# 20x20_adapter.net
KiCad netlist of a schematic drawn in EAGLE
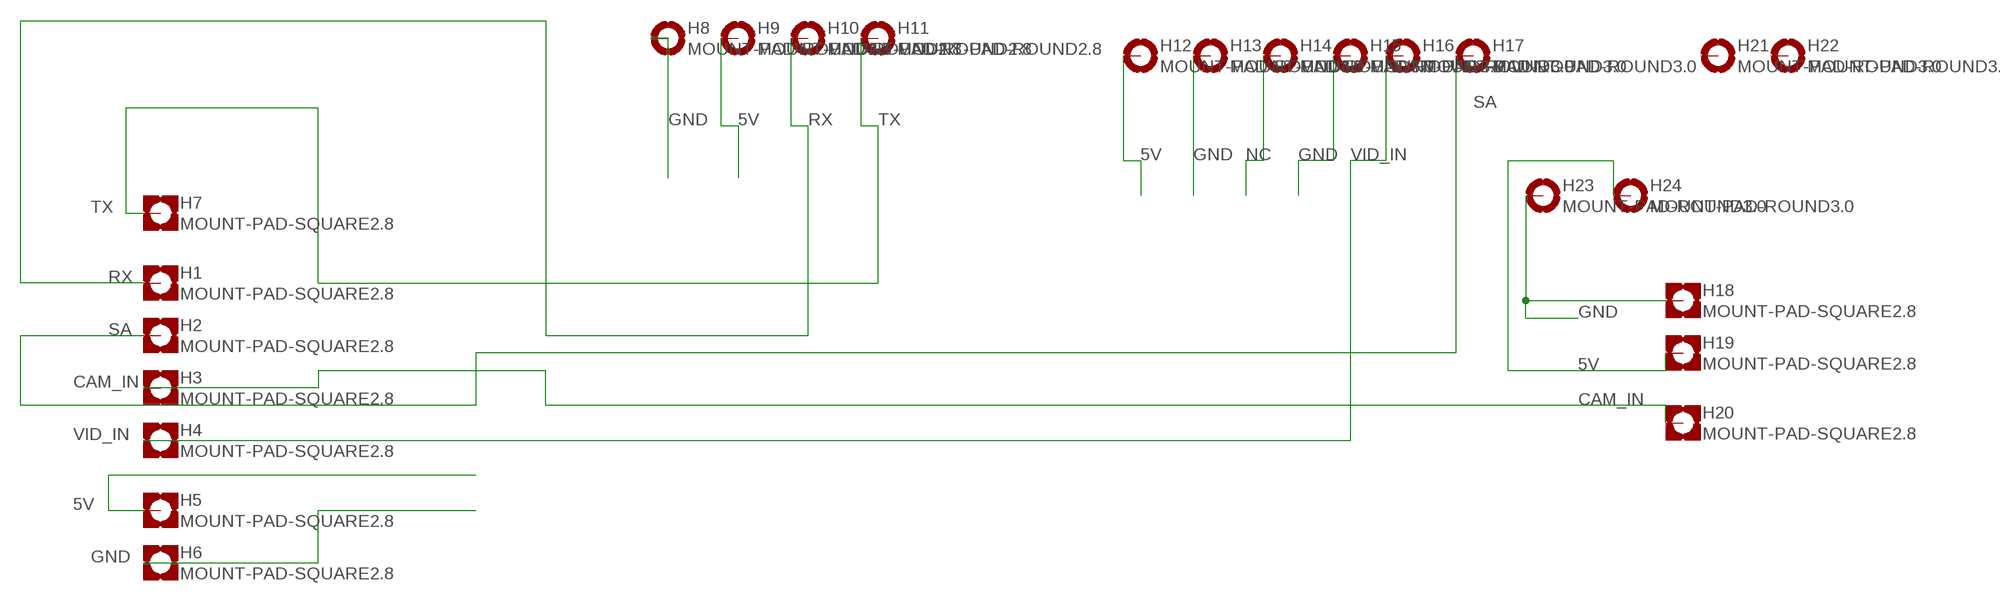
[diagram p0: schematic, sheet 1]

(export (version "E")
  (design (tool "Eeschema 10.0.6"))
  (components
    (comp (ref "H1")
      (value "MOUNT-PAD-SQUARE2.8")
      (footprint "eagle-import:2,8-PAD-SQUARE")
      (libsource (lib "eagle-import") (part "MOUNT-PAD-SQUARE2.8"))
    )
    (comp (ref "H2")
      (value "MOUNT-PAD-SQUARE2.8")
      (footprint "eagle-import:2,8-PAD-SQUARE")
      (libsource (lib "eagle-import") (part "MOUNT-PAD-SQUARE2.8"))
    )
    (comp (ref "H3")
      (value "MOUNT-PAD-SQUARE2.8")
      (footprint "eagle-import:2,8-PAD-SQUARE")
      (libsource (lib "eagle-import") (part "MOUNT-PAD-SQUARE2.8"))
    )
    (comp (ref "H4")
      (value "MOUNT-PAD-SQUARE2.8")
      (footprint "eagle-import:2,8-PAD-SQUARE")
      (libsource (lib "eagle-import") (part "MOUNT-PAD-SQUARE2.8"))
    )
    (comp (ref "H5")
      (value "MOUNT-PAD-SQUARE2.8")
      (footprint "eagle-import:2,8-PAD-SQUARE")
      (libsource (lib "eagle-import") (part "MOUNT-PAD-SQUARE2.8"))
    )
    (comp (ref "H6")
      (value "MOUNT-PAD-SQUARE2.8")
      (footprint "eagle-import:2,8-PAD-SQUARE")
      (libsource (lib "eagle-import") (part "MOUNT-PAD-SQUARE2.8"))
    )
    (comp (ref "H7")
      (value "MOUNT-PAD-SQUARE2.8")
      (footprint "eagle-import:2,8-PAD-SQUARE")
      (libsource (lib "eagle-import") (part "MOUNT-PAD-SQUARE2.8"))
    )
    (comp (ref "H8")
      (value "MOUNT-PAD-ROUND2.8")
      (footprint "eagle-import:1,0-PAD")
      (libsource (lib "eagle-import") (part "MOUNT-PAD-ROUND2.8"))
    )
    (comp (ref "H9")
      (value "MOUNT-PAD-ROUND2.8")
      (footprint "eagle-import:1,0-PAD")
      (libsource (lib "eagle-import") (part "MOUNT-PAD-ROUND2.8"))
    )
    (comp (ref "H10")
      (value "MOUNT-PAD-ROUND2.8")
      (footprint "eagle-import:1,0-PAD")
      (libsource (lib "eagle-import") (part "MOUNT-PAD-ROUND2.8"))
    )
    (comp (ref "H11")
      (value "MOUNT-PAD-ROUND2.8")
      (footprint "eagle-import:1,0-PAD")
      (libsource (lib "eagle-import") (part "MOUNT-PAD-ROUND2.8"))
    )
    (comp (ref "H12")
      (value "MOUNT-PAD-ROUND3.0")
      (footprint "eagle-import:3,0-PAD")
      (libsource (lib "eagle-import") (part "MOUNT-PAD-ROUND3.0"))
    )
    (comp (ref "H13")
      (value "MOUNT-PAD-ROUND3.0")
      (footprint "eagle-import:3,0-PAD")
      (libsource (lib "eagle-import") (part "MOUNT-PAD-ROUND3.0"))
    )
    (comp (ref "H14")
      (value "MOUNT-PAD-ROUND3.0")
      (footprint "eagle-import:3,0-PAD")
      (libsource (lib "eagle-import") (part "MOUNT-PAD-ROUND3.0"))
    )
    (comp (ref "H15")
      (value "MOUNT-PAD-ROUND3.0")
      (footprint "eagle-import:3,0-PAD")
      (libsource (lib "eagle-import") (part "MOUNT-PAD-ROUND3.0"))
    )
    (comp (ref "H16")
      (value "MOUNT-PAD-ROUND3.0")
      (footprint "eagle-import:3,0-PAD")
      (libsource (lib "eagle-import") (part "MOUNT-PAD-ROUND3.0"))
    )
    (comp (ref "H17")
      (value "MOUNT-PAD-ROUND3.0")
      (footprint "eagle-import:3,0-PAD")
      (libsource (lib "eagle-import") (part "MOUNT-PAD-ROUND3.0"))
    )
    (comp (ref "H18")
      (value "MOUNT-PAD-SQUARE2.8")
      (footprint "eagle-import:2,8-PAD-SQUARE")
      (libsource (lib "eagle-import") (part "MOUNT-PAD-SQUARE2.8"))
    )
    (comp (ref "H19")
      (value "MOUNT-PAD-SQUARE2.8")
      (footprint "eagle-import:2,8-PAD-SQUARE")
      (libsource (lib "eagle-import") (part "MOUNT-PAD-SQUARE2.8"))
    )
    (comp (ref "H20")
      (value "MOUNT-PAD-SQUARE2.8")
      (footprint "eagle-import:2,8-PAD-SQUARE")
      (libsource (lib "eagle-import") (part "MOUNT-PAD-SQUARE2.8"))
    )
    (comp (ref "H21")
      (value "MOUNT-PAD-ROUND3.0")
      (footprint "eagle-import:3,0-PAD")
      (libsource (lib "eagle-import") (part "MOUNT-PAD-ROUND3.0"))
    )
    (comp (ref "H22")
      (value "MOUNT-PAD-ROUND3.0")
      (footprint "eagle-import:3,0-PAD")
      (libsource (lib "eagle-import") (part "MOUNT-PAD-ROUND3.0"))
    )
    (comp (ref "H23")
      (value "MOUNT-PAD-ROUND3.0")
      (footprint "eagle-import:3,0-PAD")
      (libsource (lib "eagle-import") (part "MOUNT-PAD-ROUND3.0"))
    )
    (comp (ref "H24")
      (value "MOUNT-PAD-ROUND3.0")
      (footprint "eagle-import:3,0-PAD")
      (libsource (lib "eagle-import") (part "MOUNT-PAD-ROUND3.0"))
    )
  )
  (nets
    (net (code "1") (name "/5V") (class "Default")
      (node (ref "H12") (pin "B0,5") (pinfunction "MOUNT_B0,5") (pintype "passive"))
      (node (ref "H19") (pin "P$2") (pinfunction "MOUNT_P$2") (pintype "passive"))
      (node (ref "H24") (pin "B0,5") (pinfunction "MOUNT_B0,5") (pintype "passive"))
      (node (ref "H5") (pin "P$2") (pinfunction "MOUNT_P$2") (pintype "passive"))
      (node (ref "H9") (pin "B1,0") (pinfunction "MOUNT_B1,0") (pintype "passive"))
    )
    (net (code "2") (name "/CAM_IN") (class "Default")
      (node (ref "H20") (pin "P$2") (pinfunction "MOUNT_P$2") (pintype "passive"))
      (node (ref "H3") (pin "P$2") (pinfunction "MOUNT_P$2") (pintype "passive"))
    )
    (net (code "3") (name "/GND") (class "Default")
      (node (ref "H13") (pin "B0,5") (pinfunction "MOUNT_B0,5") (pintype "passive"))
      (node (ref "H15") (pin "B0,5") (pinfunction "MOUNT_B0,5") (pintype "passive"))
      (node (ref "H18") (pin "P$2") (pinfunction "MOUNT_P$2") (pintype "passive"))
      (node (ref "H23") (pin "B0,5") (pinfunction "MOUNT_B0,5") (pintype "passive"))
      (node (ref "H6") (pin "P$2") (pinfunction "MOUNT_P$2") (pintype "passive"))
      (node (ref "H8") (pin "B1,0") (pinfunction "MOUNT_B1,0") (pintype "passive"))
    )
    (net (code "4") (name "/NC") (class "Default")
      (node (ref "H14") (pin "B0,5") (pinfunction "MOUNT_B0,5") (pintype "passive"))
    )
    (net (code "5") (name "/RX") (class "Default")
      (node (ref "H1") (pin "P$2") (pinfunction "MOUNT_P$2") (pintype "passive"))
      (node (ref "H10") (pin "B1,0") (pinfunction "MOUNT_B1,0") (pintype "passive"))
    )
    (net (code "6") (name "/SA") (class "Default")
      (node (ref "H17") (pin "B0,5") (pinfunction "MOUNT_B0,5") (pintype "passive"))
      (node (ref "H2") (pin "P$2") (pinfunction "MOUNT_P$2") (pintype "passive"))
    )
    (net (code "7") (name "/TX") (class "Default")
      (node (ref "H11") (pin "B1,0") (pinfunction "MOUNT_B1,0") (pintype "passive"))
      (node (ref "H7") (pin "P$2") (pinfunction "MOUNT_P$2") (pintype "passive"))
    )
    (net (code "8") (name "/VID_IN") (class "Default")
      (node (ref "H16") (pin "B0,5") (pinfunction "MOUNT_B0,5") (pintype "passive"))
      (node (ref "H4") (pin "P$2") (pinfunction "MOUNT_P$2") (pintype "passive"))
    )
    (net (code "9") (name "unconnected-(H21-MOUNT-PadB0,5)") (class "Default")
      (node (ref "H21") (pin "B0,5") (pinfunction "MOUNT_B0,5") (pintype "passive"))
    )
    (net (code "10") (name "unconnected-(H22-MOUNT-PadB0,5)") (class "Default")
      (node (ref "H22") (pin "B0,5") (pinfunction "MOUNT_B0,5") (pintype "passive"))
    )
  )
)
